# TrabajoTecnologiaCarlos.net
KiCad netlist of a schematic drawn in Altium Designer
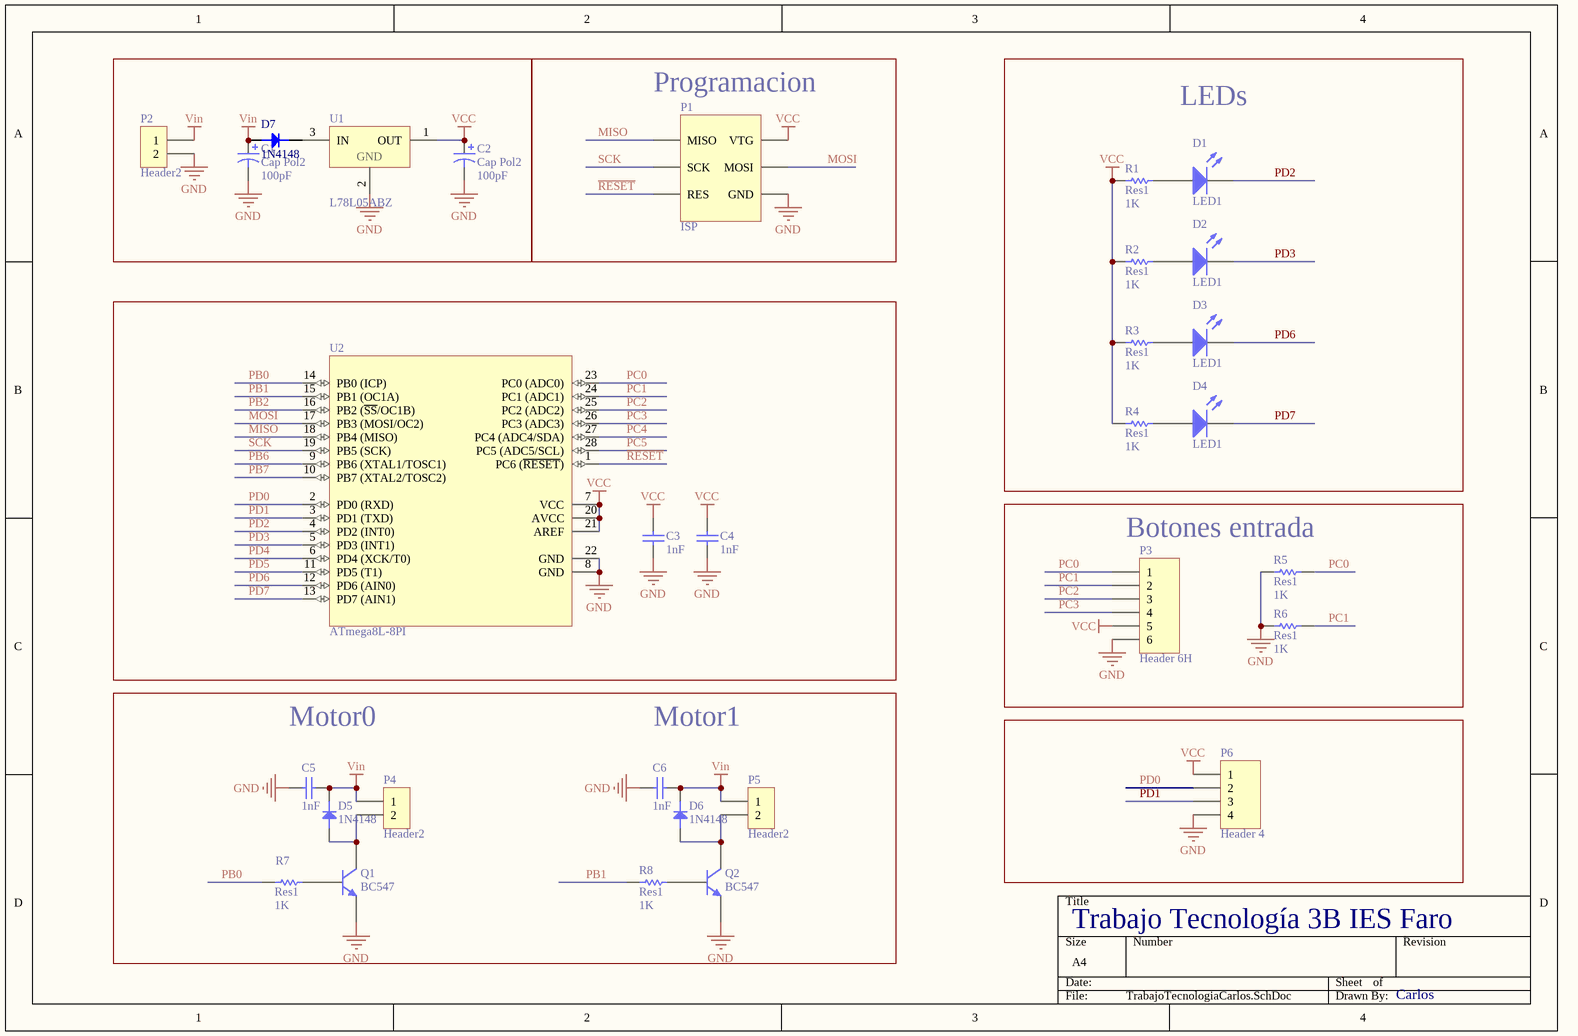
[diagram p0: TrabajoTecnologiaCarlos.SchDoc]

(export (version "E")
  (design (tool "Eeschema 10.0.6"))
  (components
    (comp (ref "C1")
      (value "Cap Pol2")
      (footprint "TC7360-2924")
      (description "Polarized Capacitor (Axial)")
      (fields (field (name "ALTIUM_VALUE") "100pF") (field (name "PUBLISHER") "Altium Limited"))
      (libsource (lib "epf") (part "Cap Pol2"))
    )
    (comp (ref "C2")
      (value "Cap Pol2")
      (footprint "TC7360-2924")
      (description "Polarized Capacitor (Axial)")
      (fields (field (name "ALTIUM_VALUE") "100pF") (field (name "PUBLISHER") "Altium Limited"))
      (libsource (lib "epf") (part "Cap Pol2"))
    )
    (comp (ref "C3")
      (value "1nF")
      (footprint "0805_CAP")
      (fields (field (name "Comment") "Capacitor"))
      (libsource (lib "epf") (part "Cap"))
    )
    (comp (ref "C4")
      (value "1nF")
      (footprint "0805_CAP")
      (fields (field (name "Comment") "Capacitor"))
      (libsource (lib "epf") (part "Cap"))
    )
    (comp (ref "C5")
      (value "1nF")
      (footprint "0805_CAP")
      (fields (field (name "Comment") "Capacitor"))
      (libsource (lib "epf") (part "Cap"))
    )
    (comp (ref "C6")
      (value "1nF")
      (footprint "0805_CAP")
      (fields (field (name "Comment") "Capacitor"))
      (libsource (lib "epf") (part "Cap"))
    )
    (comp (ref "D1")
      (value "LED1")
      (footprint "LED-1")
      (description "Typical RED GaAs LED")
      (fields (field (name "PUBLISHER") "Altium Limited"))
      (libsource (lib "Miscellaneous Devices") (part "LED1"))
    )
    (comp (ref "D2")
      (value "LED1")
      (footprint "LED-1")
      (description "Typical RED GaAs LED")
      (fields (field (name "PUBLISHER") "Altium Limited"))
      (libsource (lib "Miscellaneous Devices") (part "LED1"))
    )
    (comp (ref "D3")
      (value "LED1")
      (footprint "LED-1")
      (description "Typical RED GaAs LED")
      (fields (field (name "PUBLISHER") "Altium Limited"))
      (libsource (lib "Miscellaneous Devices") (part "LED1"))
    )
    (comp (ref "D4")
      (value "LED1")
      (footprint "LED-1")
      (description "Typical RED GaAs LED")
      (fields (field (name "PUBLISHER") "Altium Limited"))
      (libsource (lib "Miscellaneous Devices") (part "LED1"))
    )
    (comp (ref "D5") (value "1N4148") (footprint "1N4148SMD") (libsource (lib "epf") (part "1N4148")))
    (comp (ref "D6") (value "1N4148") (footprint "1N4148SMD") (libsource (lib "epf") (part "1N4148")))
    (comp (ref "D7") (value "1N4148") (footprint "1N4148SMD") (libsource (lib "epf") (part "1N4148")))
    (comp (ref "P1") (value "ISP") (footprint "AVR_ISP") (libsource (lib "epf") (part "AVR_ISP")))
    (comp (ref "P2") (value "Header2") (footprint "Header2Macho") (libsource (lib "") (part "Header2_1")))
    (comp (ref "P3")
      (value "Header 6H")
      (footprint "HDR1X6H")
      (description "Header, 6-Pin, Right Angle")
      (fields (field (name "PUBLISHER") "Altium Limited"))
      (libsource (lib "Miscellaneous Connectors") (part "Header 6H"))
    )
    (comp (ref "P4") (value "Header2") (footprint "Header2Macho") (libsource (lib "epf") (part "Header2")))
    (comp (ref "P5") (value "Header2") (footprint "Header2Macho") (libsource (lib "epf") (part "Header2")))
    (comp (ref "P6")
      (value "Header 4")
      (footprint "HDR1X4")
      (description "Header, 4-Pin")
      (fields (field (name "PUBLISHER") "Altium Limited"))
      (libsource (lib "Miscellaneous Connectors") (part "Header 4"))
    )
    (comp (ref "Q1") (value "BC547") (footprint "TO92") (libsource (lib "epf") (part "BC547")))
    (comp (ref "Q2") (value "BC547") (footprint "TO92") (libsource (lib "epf") (part "BC547")))
    (comp (ref "R1")
      (value "Res1")
      (footprint "AXIAL-0.3 3D")
      (description "Resistor")
      (fields (field (name "ALTIUM_VALUE") "1K") (field (name "PUBLISHER") "Altium Limited"))
      (libsource (lib "epf") (part "Res1"))
    )
    (comp (ref "R2")
      (value "Res1")
      (footprint "AXIAL-0.3 3D")
      (description "Resistor")
      (fields (field (name "ALTIUM_VALUE") "1K") (field (name "PUBLISHER") "Altium Limited"))
      (libsource (lib "epf") (part "Res1"))
    )
    (comp (ref "R3")
      (value "Res1")
      (footprint "AXIAL-0.3 3D")
      (description "Resistor")
      (fields (field (name "ALTIUM_VALUE") "1K") (field (name "PUBLISHER") "Altium Limited"))
      (libsource (lib "epf") (part "Res1"))
    )
    (comp (ref "R4")
      (value "Res1")
      (footprint "AXIAL-0.3 3D")
      (description "Resistor")
      (fields (field (name "ALTIUM_VALUE") "1K") (field (name "PUBLISHER") "Altium Limited"))
      (libsource (lib "epf") (part "Res1"))
    )
    (comp (ref "R5")
      (value "Res1")
      (footprint "AXIAL-0.3 3D")
      (description "Resistor")
      (fields (field (name "ALTIUM_VALUE") "1K") (field (name "PUBLISHER") "Altium Limited"))
      (libsource (lib "epf") (part "Res1"))
    )
    (comp (ref "R6")
      (value "Res1")
      (footprint "AXIAL-0.3 3D")
      (description "Resistor")
      (fields (field (name "ALTIUM_VALUE") "1K") (field (name "PUBLISHER") "Altium Limited"))
      (libsource (lib "epf") (part "Res1"))
    )
    (comp (ref "R7")
      (value "Res1")
      (footprint "AXIAL-0.3 3D")
      (description "Resistor")
      (fields (field (name "ALTIUM_VALUE") "1K") (field (name "PUBLISHER") "Altium Limited"))
      (libsource (lib "epf") (part "Res1"))
    )
    (comp (ref "R8")
      (value "Res1")
      (footprint "AXIAL-0.3 3D")
      (description "Resistor")
      (fields (field (name "ALTIUM_VALUE") "1K") (field (name "PUBLISHER") "Altium Limited"))
      (libsource (lib "epf") (part "Res1"))
    )
    (comp (ref "U1")
      (value "L78L05ABZ")
      (footprint "TO92V2")
      (description "Positive Voltage Regulator")
      (fields (field (name "PUBLISHER") "Altium Limited"))
      (libsource (lib "ST Power Mgt Voltage Regulator") (part "L78L05ABZ"))
    )
    (comp (ref "U2")
      (value "ATmega8L-8PI")
      (footprint "28P3")
      (description "8-Bit AVR Microcontroller with 8K Bytes of In-System Programmable Flash Memory")
      (fields (field (name "PUBLISHER") "Altium Limited"))
      (libsource (lib "epf") (part "ATmega8L-8PI"))
    )
  )
  (nets
    (net (code "1") (name "/MISO") (class "Default")
      (node (ref "P1") (pin "0") (pinfunction "MISO_0") (pintype "passive"))
      (node (ref "U2") (pin "18") (pinfunction "PB4_(MISO)_18") (pintype "bidirectional"))
    )
    (net (code "2") (name "/MOSI") (class "Default")
      (node (ref "P1") (pin "3") (pinfunction "MOSI_3") (pintype "passive"))
      (node (ref "U2") (pin "17") (pinfunction "PB3_(MOSI/OC2)_17") (pintype "bidirectional"))
    )
    (net (code "3") (name "/PB0") (class "Default")
      (node (ref "R7") (pin "1") (pinfunction "1_1") (pintype "passive"))
      (node (ref "U2") (pin "14") (pinfunction "PB0_(ICP)_14") (pintype "bidirectional"))
    )
    (net (code "4") (name "/PB1") (class "Default")
      (node (ref "R8") (pin "1") (pinfunction "1_1") (pintype "passive"))
      (node (ref "U2") (pin "15") (pinfunction "PB1_(OC1A)_15") (pintype "bidirectional"))
    )
    (net (code "5") (name "/PB2") (class "Default")
      (node (ref "U2") (pin "16") (pinfunction "PB2_(~{SS}/OC1B)_16") (pintype "bidirectional"))
    )
    (net (code "6") (name "/PB6") (class "Default")
      (node (ref "U2") (pin "9") (pinfunction "PB6_(XTAL1/TOSC1)_9") (pintype "bidirectional"))
    )
    (net (code "7") (name "/PB7") (class "Default")
      (node (ref "U2") (pin "10") (pinfunction "PB7_(XTAL2/TOSC2)_10") (pintype "bidirectional"))
    )
    (net (code "8") (name "/PC0") (class "Default")
      (node (ref "P3") (pin "1") (pinfunction "1_1") (pintype "passive"))
      (node (ref "R5") (pin "1") (pinfunction "1_1") (pintype "passive"))
      (node (ref "U2") (pin "23") (pinfunction "PC0_(ADC0)_23") (pintype "bidirectional"))
    )
    (net (code "9") (name "/PC1") (class "Default")
      (node (ref "P3") (pin "2") (pinfunction "2_2") (pintype "passive"))
      (node (ref "R6") (pin "1") (pinfunction "1_1") (pintype "passive"))
      (node (ref "U2") (pin "24") (pinfunction "PC1_(ADC1)_24") (pintype "bidirectional"))
    )
    (net (code "10") (name "/PC2") (class "Default")
      (node (ref "P3") (pin "3") (pinfunction "3_3") (pintype "passive"))
      (node (ref "U2") (pin "25") (pinfunction "PC2_(ADC2)_25") (pintype "bidirectional"))
    )
    (net (code "11") (name "/PC3") (class "Default")
      (node (ref "P3") (pin "4") (pinfunction "4_4") (pintype "passive"))
      (node (ref "U2") (pin "26") (pinfunction "PC3_(ADC3)_26") (pintype "bidirectional"))
    )
    (net (code "12") (name "/PC4") (class "Default")
      (node (ref "U2") (pin "27") (pinfunction "PC4_(ADC4/SDA)_27") (pintype "bidirectional"))
    )
    (net (code "13") (name "/PC5") (class "Default")
      (node (ref "U2") (pin "28") (pinfunction "PC5_(ADC5/SCL)_28") (pintype "bidirectional"))
    )
    (net (code "14") (name "/PD0") (class "Default")
      (node (ref "P6") (pin "2") (pinfunction "2_2") (pintype "passive"))
      (node (ref "U2") (pin "2") (pinfunction "PD0_(RXD)_2") (pintype "bidirectional"))
    )
    (net (code "15") (name "/PD1") (class "Default")
      (node (ref "P6") (pin "3") (pinfunction "3_3") (pintype "passive"))
      (node (ref "U2") (pin "3") (pinfunction "PD1_(TXD)_3") (pintype "bidirectional"))
    )
    (net (code "16") (name "/PD2") (class "Default")
      (node (ref "D1") (pin "2") (pinfunction "K_2") (pintype "passive"))
      (node (ref "U2") (pin "4") (pinfunction "PD2_(INT0)_4") (pintype "bidirectional"))
    )
    (net (code "17") (name "/PD3") (class "Default")
      (node (ref "D2") (pin "2") (pinfunction "K_2") (pintype "passive"))
      (node (ref "U2") (pin "5") (pinfunction "PD3_(INT1)_5") (pintype "bidirectional"))
    )
    (net (code "18") (name "/PD4") (class "Default")
      (node (ref "U2") (pin "6") (pinfunction "PD4_(XCK/T0)_6") (pintype "bidirectional"))
    )
    (net (code "19") (name "/PD5") (class "Default")
      (node (ref "U2") (pin "11") (pinfunction "PD5_(T1)_11") (pintype "bidirectional"))
    )
    (net (code "20") (name "/PD6") (class "Default")
      (node (ref "D3") (pin "2") (pinfunction "K_2") (pintype "passive"))
      (node (ref "U2") (pin "12") (pinfunction "PD6_(AIN0)_12") (pintype "bidirectional"))
    )
    (net (code "21") (name "/PD7") (class "Default")
      (node (ref "D4") (pin "2") (pinfunction "K_2") (pintype "passive"))
      (node (ref "U2") (pin "13") (pinfunction "PD7_(AIN1)_13") (pintype "bidirectional"))
    )
    (net (code "22") (name "/SCK") (class "Default")
      (node (ref "P1") (pin "2") (pinfunction "SCK_2") (pintype "passive"))
      (node (ref "U2") (pin "19") (pinfunction "PB5_(SCK)_19") (pintype "bidirectional"))
    )
    (net (code "23") (name "/~{RESET}") (class "Default")
      (node (ref "P1") (pin "4") (pinfunction "RES_4") (pintype "passive"))
      (node (ref "U2") (pin "1") (pinfunction "PC6_(~{RESET})_1") (pintype "bidirectional"))
    )
    (net (code "24") (name "GND") (class "Default")
      (node (ref "C1") (pin "2") (pinfunction "2_2") (pintype "passive"))
      (node (ref "C2") (pin "2") (pinfunction "2_2") (pintype "passive"))
      (node (ref "C3") (pin "1") (pinfunction "1_1") (pintype "passive"))
      (node (ref "C4") (pin "1") (pinfunction "1_1") (pintype "passive"))
      (node (ref "C5") (pin "2") (pinfunction "2_2") (pintype "passive"))
      (node (ref "C6") (pin "2") (pinfunction "2_2") (pintype "passive"))
      (node (ref "P1") (pin "5") (pinfunction "GND_5") (pintype "passive"))
      (node (ref "P2") (pin "2") (pinfunction "2_2") (pintype "passive"))
      (node (ref "P3") (pin "6") (pinfunction "6_6") (pintype "passive"))
      (node (ref "P6") (pin "4") (pinfunction "4_4") (pintype "passive"))
      (node (ref "Q1") (pin "1") (pinfunction "E_1") (pintype "passive"))
      (node (ref "Q2") (pin "1") (pinfunction "E_1") (pintype "passive"))
      (node (ref "R5") (pin "2") (pinfunction "2_2") (pintype "passive"))
      (node (ref "R6") (pin "2") (pinfunction "2_2") (pintype "passive"))
      (node (ref "U1") (pin "2") (pinfunction "GND_2") (pintype "power_in"))
      (node (ref "U2") (pin "22") (pinfunction "GND_22") (pintype "power_in"))
      (node (ref "U2") (pin "8") (pinfunction "GND_8") (pintype "power_in"))
    )
    (net (code "25") (name "Net-(D1-A)") (class "Default")
      (node (ref "D1") (pin "1") (pinfunction "A_1") (pintype "passive"))
      (node (ref "R1") (pin "2") (pinfunction "2_2") (pintype "passive"))
    )
    (net (code "26") (name "Net-(D2-A)") (class "Default")
      (node (ref "D2") (pin "1") (pinfunction "A_1") (pintype "passive"))
      (node (ref "R2") (pin "2") (pinfunction "2_2") (pintype "passive"))
    )
    (net (code "27") (name "Net-(D3-A)") (class "Default")
      (node (ref "D3") (pin "1") (pinfunction "A_1") (pintype "passive"))
      (node (ref "R3") (pin "2") (pinfunction "2_2") (pintype "passive"))
    )
    (net (code "28") (name "Net-(D4-A)") (class "Default")
      (node (ref "D4") (pin "1") (pinfunction "A_1") (pintype "passive"))
      (node (ref "R4") (pin "2") (pinfunction "2_2") (pintype "passive"))
    )
    (net (code "29") (name "Net-(D5-A)") (class "Default")
      (node (ref "D5") (pin "1") (pinfunction "A_1") (pintype "passive"))
      (node (ref "P4") (pin "2") (pinfunction "2_2") (pintype "passive"))
      (node (ref "Q1") (pin "3") (pinfunction "C_3") (pintype "passive"))
    )
    (net (code "30") (name "Net-(D6-A)") (class "Default")
      (node (ref "D6") (pin "1") (pinfunction "A_1") (pintype "passive"))
      (node (ref "P5") (pin "2") (pinfunction "2_2") (pintype "passive"))
      (node (ref "Q2") (pin "3") (pinfunction "C_3") (pintype "passive"))
    )
    (net (code "31") (name "Net-(D7-K)") (class "Default")
      (node (ref "D7") (pin "2") (pinfunction "K_2") (pintype "passive"))
      (node (ref "U1") (pin "3") (pinfunction "IN_3") (pintype "power_in"))
    )
    (net (code "32") (name "Net-(Q1-B)") (class "Default")
      (node (ref "Q1") (pin "2") (pinfunction "B_2") (pintype "passive"))
      (node (ref "R7") (pin "2") (pinfunction "2_2") (pintype "passive"))
    )
    (net (code "33") (name "Net-(Q2-B)") (class "Default")
      (node (ref "Q2") (pin "2") (pinfunction "B_2") (pintype "passive"))
      (node (ref "R8") (pin "2") (pinfunction "2_2") (pintype "passive"))
    )
    (net (code "34") (name "VCC") (class "Default")
      (node (ref "C2") (pin "1") (pinfunction "1_1") (pintype "passive"))
      (node (ref "C3") (pin "2") (pinfunction "2_2") (pintype "passive"))
      (node (ref "C4") (pin "2") (pinfunction "2_2") (pintype "passive"))
      (node (ref "P1") (pin "1") (pinfunction "VTG_1") (pintype "passive"))
      (node (ref "P3") (pin "5") (pinfunction "5_5") (pintype "passive"))
      (node (ref "P6") (pin "1") (pinfunction "1_1") (pintype "passive"))
      (node (ref "R1") (pin "1") (pinfunction "1_1") (pintype "passive"))
      (node (ref "R2") (pin "1") (pinfunction "1_1") (pintype "passive"))
      (node (ref "R3") (pin "1") (pinfunction "1_1") (pintype "passive"))
      (node (ref "R4") (pin "1") (pinfunction "1_1") (pintype "passive"))
      (node (ref "U1") (pin "1") (pinfunction "OUT_1") (pintype "power_in"))
      (node (ref "U2") (pin "20") (pinfunction "AVCC_20") (pintype "power_in"))
      (node (ref "U2") (pin "21") (pinfunction "AREF_21") (pintype "passive"))
      (node (ref "U2") (pin "7") (pinfunction "VCC_7") (pintype "power_in"))
    )
    (net (code "35") (name "Vin") (class "Default")
      (node (ref "C1") (pin "1") (pinfunction "1_1") (pintype "passive"))
      (node (ref "C5") (pin "1") (pinfunction "1_1") (pintype "passive"))
      (node (ref "C6") (pin "1") (pinfunction "1_1") (pintype "passive"))
      (node (ref "D5") (pin "2") (pinfunction "K_2") (pintype "passive"))
      (node (ref "D6") (pin "2") (pinfunction "K_2") (pintype "passive"))
      (node (ref "D7") (pin "1") (pinfunction "A_1") (pintype "passive"))
      (node (ref "P2") (pin "1") (pinfunction "1_1") (pintype "passive"))
      (node (ref "P4") (pin "1") (pinfunction "1_1") (pintype "passive"))
      (node (ref "P5") (pin "1") (pinfunction "1_1") (pintype "passive"))
    )
  )
)
